# Switching_schematic_2022-05-04.net
KiCad netlist of a schematic drawn in Altium Designer
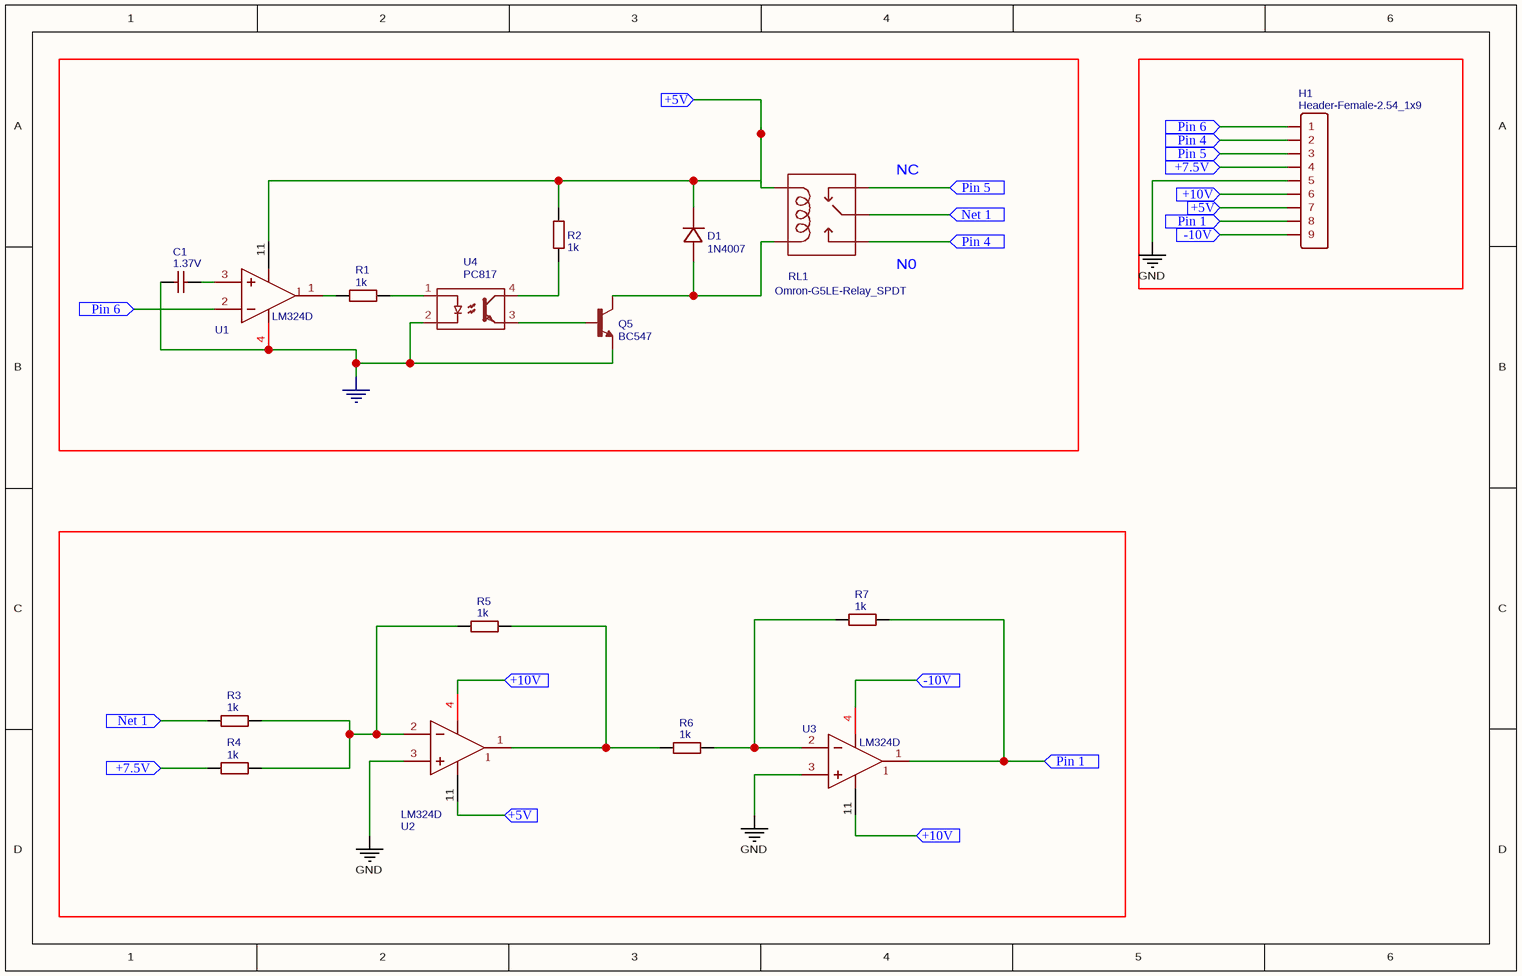
[diagram p0: Switching_schematic_2022-05-04.schdoc]

(export (version "E")
  (design (tool "Eeschema 10.0.6"))
  (components
    (comp (ref "C1")
      (value "1.37V")
      (fields
        (field (name "BOM_MANUFACTURER PART") "0.1UF(104) +-20% 63v")
        (field (name "BOM_SUPPLIER PART") "C19355")
      )
      (libsource (lib "altium-import") (part "root_0_1.37V_"))
    )
    (comp (ref "D1")
      (value "1N4007")
      (fields (field (name "BOM_MANUFACTURER PART") "?"))
      (libsource (lib "altium-import") (part "root_1_1N4007_"))
    )
    (comp (ref "H1")
      (value "Header-Female-2.54_1x9")
      (fields
        (field (name "BOM_MANUFACTURER PART") "2.54mm 1*9 Straight Female header")
        (field (name "BOM_SUPPLIER PART") "C39576")
      )
      (libsource (lib "altium-import") (part "root_0_Header-Female-2.54_1x9_"))
    )
    (comp (ref "Q5")
      (value "BC547")
      (description "Generic NPN BJT")
      (fields (field (name "BOM_MANUFACTURER PART") "?") (field (name "CONTRIBUTOR") "SparkFun"))
      (libsource (lib "altium-import") (part "root_0_BC547_"))
    )
    (comp (ref "R1")
      (value "1k")
      (fields
        (field (name "POWER") "1/4W")
        (field (name "TOLERANCE") "±1%")
        (field (name "BOM_SUPPLIER PART") "E57439")
      )
      (libsource (lib "altium-import") (part "root_2_1k_"))
    )
    (comp (ref "R2")
      (value "1k")
      (fields
        (field (name "POWER") "1/4W")
        (field (name "TOLERANCE") "±1%")
        (field (name "BOM_SUPPLIER PART") "E57439")
      )
      (libsource (lib "altium-import") (part "root_1_1k_"))
    )
    (comp (ref "R3")
      (value "1k")
      (fields
        (field (name "POWER") "1/4W")
        (field (name "TOLERANCE") "±1%")
        (field (name "BOM_SUPPLIER PART") "E57439")
      )
      (libsource (lib "altium-import") (part "root_2_1k_"))
    )
    (comp (ref "R4")
      (value "1k")
      (fields
        (field (name "POWER") "1/4W")
        (field (name "TOLERANCE") "±1%")
        (field (name "BOM_SUPPLIER PART") "E57439")
      )
      (libsource (lib "altium-import") (part "root_2_1k_"))
    )
    (comp (ref "R5")
      (value "1k")
      (fields
        (field (name "POWER") "1/4W")
        (field (name "TOLERANCE") "±1%")
        (field (name "BOM_SUPPLIER PART") "E57439")
      )
      (libsource (lib "altium-import") (part "root_2_1k_"))
    )
    (comp (ref "R6")
      (value "1k")
      (fields
        (field (name "POWER") "1/4W")
        (field (name "TOLERANCE") "±1%")
        (field (name "BOM_SUPPLIER PART") "E57439")
      )
      (libsource (lib "altium-import") (part "root_2_1k_"))
    )
    (comp (ref "R7")
      (value "1k")
      (fields
        (field (name "POWER") "1/4W")
        (field (name "TOLERANCE") "±1%")
        (field (name "BOM_SUPPLIER PART") "E57439")
      )
      (libsource (lib "altium-import") (part "root_2_1k_"))
    )
    (comp (ref "RL1")
      (value "Omron-G5LE-Relay_SPDT")
      (fields (field (name "BOM_MANUFACTURER PART") "?"))
      (libsource (lib "altium-import") (part "root_0_Omron-G5LE-Relay_SPDT_"))
    )
    (comp (ref "U1")
      (value "LM324D")
      (fields
        (field (name "BOM_SUPPLIER PART") "C2935189")
        (field (name "SUBPART_NO") "1")
        (field (name "CONTRIBUTOR") "LCSC")
      )
      (libsource (lib "") (part "root_0_LM324D__1"))
    )
    (comp (ref "U2")
      (value "LM324D")
      (fields
        (field (name "BOM_SUPPLIER PART") "C2935189")
        (field (name "SUBPART_NO") "1")
        (field (name "CONTRIBUTOR") "LCSC")
      )
      (libsource (lib "altium-import") (part "root_0_LM324D_"))
    )
    (comp (ref "U3")
      (value "LM324D")
      (fields
        (field (name "BOM_SUPPLIER PART") "C2935189")
        (field (name "SUBPART_NO") "1")
        (field (name "CONTRIBUTOR") "LCSC")
      )
      (libsource (lib "altium-import") (part "root_0_LM324D_"))
    )
    (comp (ref "U4")
      (value "PC817")
      (fields (field (name "BOM_MANUFACTURER PART") "?"))
      (libsource (lib "altium-import") (part "root_0_PC817_"))
    )
  )
  (nets
    (net (code "1") (name "/+5V") (class "Default")
      (node (ref "D1") (pin "2") (pinfunction "C_2") (pintype "passive"))
      (node (ref "H1") (pin "7") (pinfunction "7_7") (pintype "passive"))
      (node (ref "R2") (pin "2") (pinfunction "2_2") (pintype "passive"))
      (node (ref "RL1") (pin "2") (pinfunction "COIL2_2") (pintype "passive"))
      (node (ref "U1") (pin "11") (pinfunction "VCC-_11") (pintype "passive"))
      (node (ref "U2") (pin "11") (pinfunction "VCC-_11") (pintype "passive"))
    )
    (net (code "2") (name "/+7.5V") (class "Default")
      (node (ref "H1") (pin "4") (pinfunction "4_4") (pintype "passive"))
      (node (ref "R4") (pin "2") (pinfunction "2_2") (pintype "passive"))
    )
    (net (code "3") (name "/+10V") (class "Default")
      (node (ref "H1") (pin "6") (pinfunction "6_6") (pintype "passive"))
      (node (ref "U2") (pin "4") (pinfunction "VCC+_4") (pintype "passive"))
      (node (ref "U3") (pin "11") (pinfunction "VCC-_11") (pintype "passive"))
    )
    (net (code "4") (name "/-10V") (class "Default")
      (node (ref "H1") (pin "9") (pinfunction "9_9") (pintype "passive"))
      (node (ref "U3") (pin "4") (pinfunction "VCC+_4") (pintype "passive"))
    )
    (net (code "5") (name "/Net 1") (class "Default")
      (node (ref "R3") (pin "2") (pinfunction "2_2") (pintype "passive"))
      (node (ref "RL1") (pin "1") (pinfunction "MAIN_1") (pintype "passive"))
    )
    (net (code "6") (name "/Pin 1") (class "Default")
      (node (ref "H1") (pin "8") (pinfunction "8_8") (pintype "passive"))
      (node (ref "R7") (pin "1") (pinfunction "1_1") (pintype "passive"))
      (node (ref "U3") (pin "1") (pinfunction "OUT1_1") (pintype "passive"))
    )
    (net (code "7") (name "/Pin 4") (class "Default")
      (node (ref "H1") (pin "2") (pinfunction "2_2") (pintype "passive"))
      (node (ref "RL1") (pin "3") (pinfunction "NO_3") (pintype "passive"))
    )
    (net (code "8") (name "/Pin 5") (class "Default")
      (node (ref "H1") (pin "3") (pinfunction "3_3") (pintype "passive"))
      (node (ref "RL1") (pin "4") (pinfunction "NC_4") (pintype "passive"))
    )
    (net (code "9") (name "/Pin 6") (class "Default")
      (node (ref "H1") (pin "1") (pinfunction "1_1") (pintype "passive"))
      (node (ref "U1") (pin "2") (pinfunction "IN1-_2") (pintype "passive"))
    )
    (net (code "10") (name "GND") (class "Default")
      (node (ref "C1") (pin "1") (pinfunction "1_1") (pintype "passive"))
      (node (ref "H1") (pin "5") (pinfunction "5_5") (pintype "passive"))
      (node (ref "Q5") (pin "3") (pinfunction "E_3") (pintype "passive"))
      (node (ref "U1") (pin "4") (pinfunction "VCC+_4") (pintype "passive"))
      (node (ref "U2") (pin "3") (pinfunction "IN1+_3") (pintype "passive"))
      (node (ref "U3") (pin "3") (pinfunction "IN1+_3") (pintype "passive"))
      (node (ref "U4") (pin "2") (pinfunction "2_2") (pintype "passive"))
    )
    (net (code "11") (name "Net-(D1-A)") (class "Default")
      (node (ref "D1") (pin "1") (pinfunction "A_1") (pintype "passive"))
      (node (ref "Q5") (pin "1") (pinfunction "C_1") (pintype "passive"))
      (node (ref "RL1") (pin "5") (pinfunction "COIL1_5") (pintype "passive"))
    )
    (net (code "12") (name "Net-(Q5-B)") (class "Default")
      (node (ref "Q5") (pin "2") (pinfunction "B_2") (pintype "passive"))
      (node (ref "U4") (pin "3") (pinfunction "3_3") (pintype "passive"))
    )
    (net (code "13") (name "Net-(R1-Pad1)") (class "Default")
      (node (ref "R1") (pin "1") (pinfunction "1_1") (pintype "passive"))
      (node (ref "U4") (pin "1") (pinfunction "1_1") (pintype "passive"))
    )
    (net (code "14") (name "Net-(R2-Pad1)") (class "Default")
      (node (ref "R2") (pin "1") (pinfunction "1_1") (pintype "passive"))
      (node (ref "U4") (pin "4") (pinfunction "4_4") (pintype "passive"))
    )
    (net (code "15") (name "Net-(U1-IN1+)") (class "Default")
      (node (ref "C1") (pin "2") (pinfunction "2_2") (pintype "passive"))
      (node (ref "U1") (pin "3") (pinfunction "IN1+_3") (pintype "passive"))
    )
    (net (code "16") (name "Net-(U1-OUT1)") (class "Default")
      (node (ref "R1") (pin "2") (pinfunction "2_2") (pintype "passive"))
      (node (ref "U1") (pin "1") (pinfunction "OUT1_1") (pintype "passive"))
    )
    (net (code "17") (name "Net-(U2-IN1-)") (class "Default")
      (node (ref "R3") (pin "1") (pinfunction "1_1") (pintype "passive"))
      (node (ref "R4") (pin "1") (pinfunction "1_1") (pintype "passive"))
      (node (ref "R5") (pin "2") (pinfunction "2_2") (pintype "passive"))
      (node (ref "U2") (pin "2") (pinfunction "IN1-_2") (pintype "passive"))
    )
    (net (code "18") (name "Net-(U2-OUT1)") (class "Default")
      (node (ref "R5") (pin "1") (pinfunction "1_1") (pintype "passive"))
      (node (ref "R6") (pin "2") (pinfunction "2_2") (pintype "passive"))
      (node (ref "U2") (pin "1") (pinfunction "OUT1_1") (pintype "passive"))
    )
    (net (code "19") (name "Net-(U3-IN1-)") (class "Default")
      (node (ref "R6") (pin "1") (pinfunction "1_1") (pintype "passive"))
      (node (ref "R7") (pin "2") (pinfunction "2_2") (pintype "passive"))
      (node (ref "U3") (pin "2") (pinfunction "IN1-_2") (pintype "passive"))
    )
  )
)
